# Version1_2.net
KiCad netlist of a schematic drawn in EAGLE
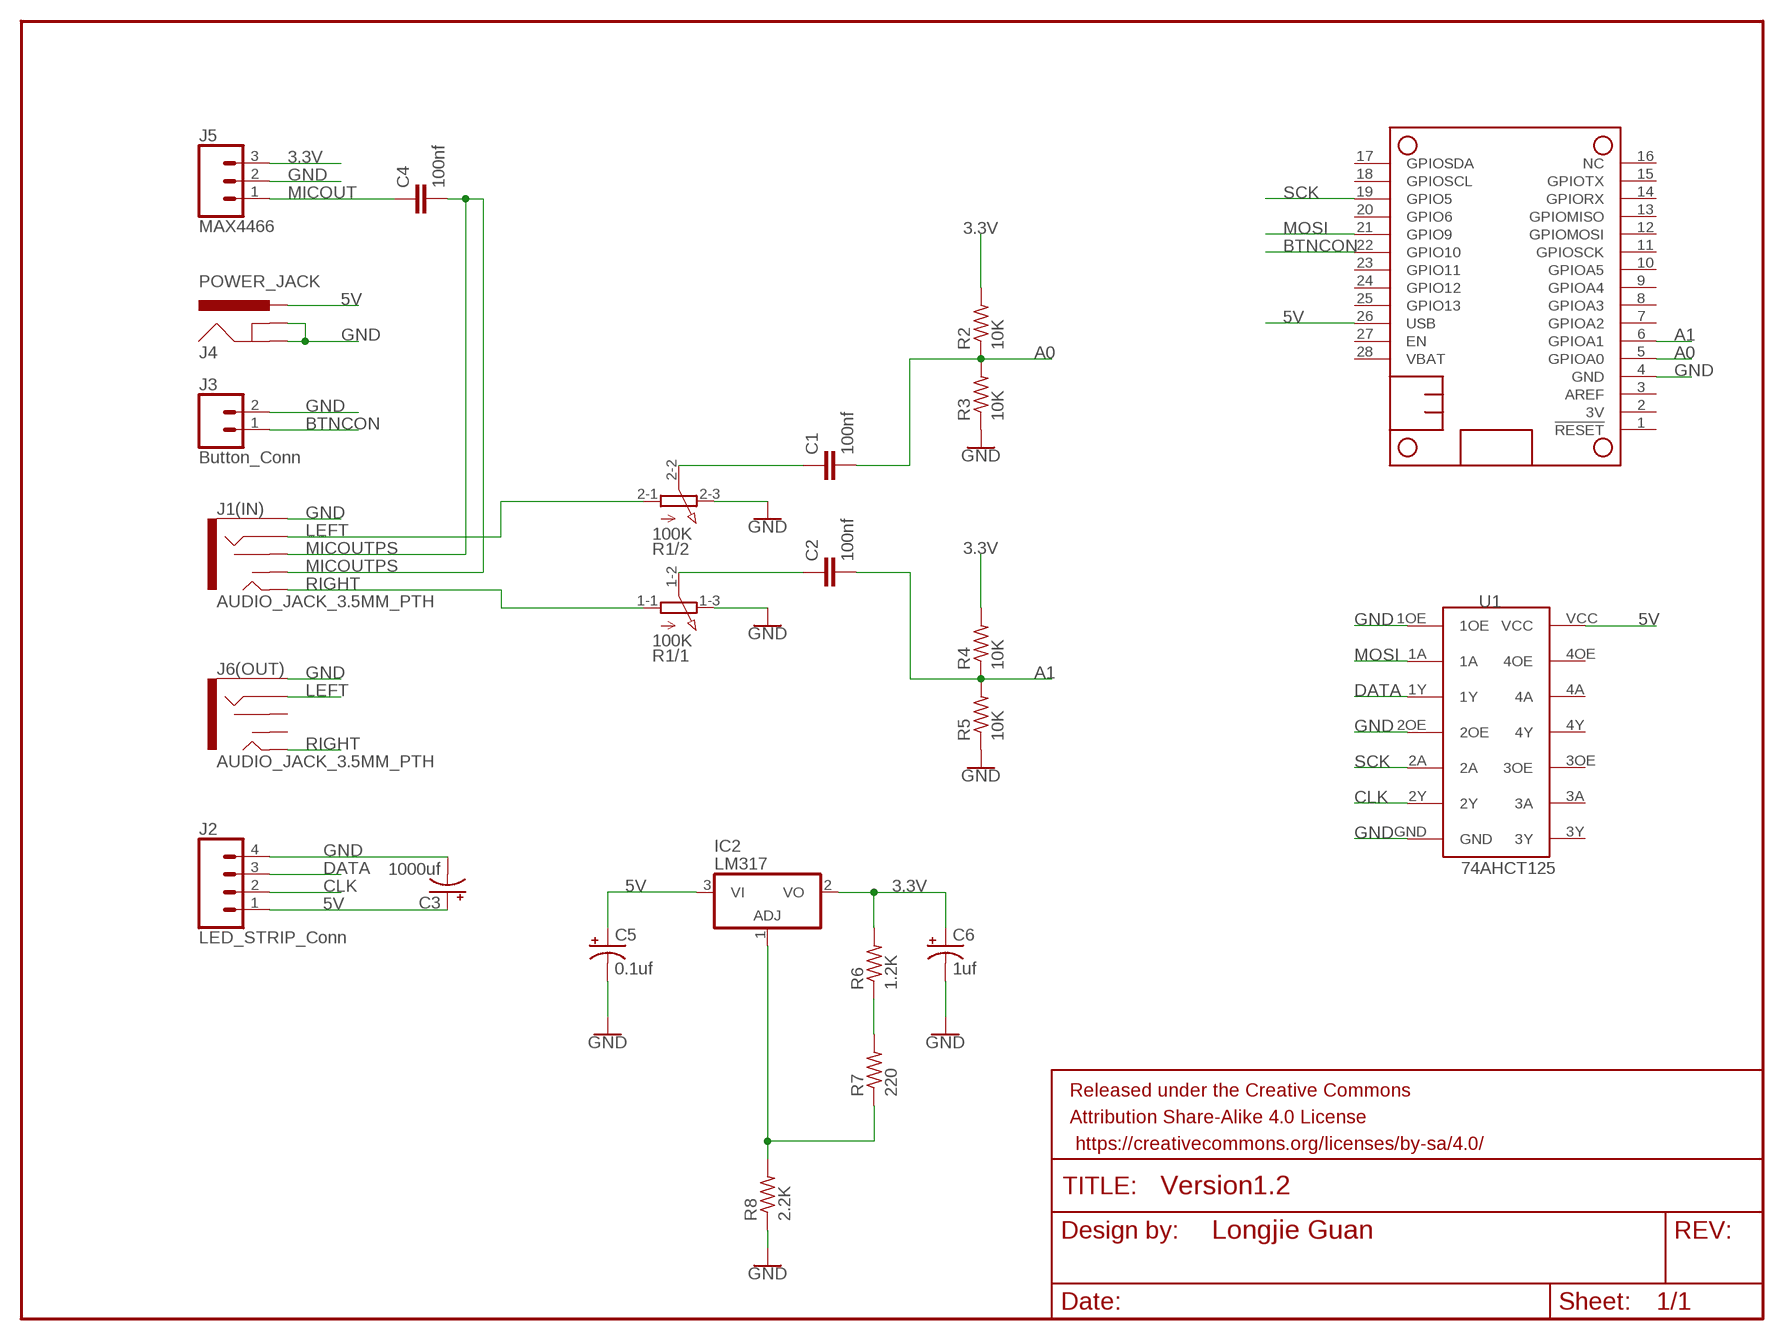
[diagram p0: schematic, sheet 1]

(export (version "E")
  (design (tool "Eeschema 10.0.6"))
  (components
    (comp (ref "C1")
      (value "100nf")
      (footprint "eagle-import:C2.5-2")
      (libsource (lib "eagle-import") (part "C2.5/2"))
    )
    (comp (ref "C2")
      (value "100nf")
      (footprint "eagle-import:C2.5-2")
      (libsource (lib "eagle-import") (part "C2.5/2"))
    )
    (comp (ref "C3")
      (value "1000uf")
      (footprint "eagle-import:B45181A")
      (libsource (lib "eagle-import") (part "CPOL-USB45181A"))
    )
    (comp (ref "C4")
      (value "100nf")
      (footprint "eagle-import:C2.5-2")
      (libsource (lib "eagle-import") (part "C2.5/2"))
    )
    (comp (ref "C5")
      (value "0.1uf")
      (footprint "eagle-import:B45181A")
      (libsource (lib "eagle-import") (part "CPOL-USB45181A"))
    )
    (comp (ref "C6")
      (value "1uf")
      (footprint "eagle-import:B45181A")
      (libsource (lib "eagle-import") (part "CPOL-USB45181A"))
    )
    (comp (ref "FRAME1")
      (value "FRAME-LETTERNO_PACKAGE")
      (footprint "eagle-import:DUMMY")
      (fields (field (name "DESIGNER") "Nobody"))
      (libsource (lib "eagle-import") (part "FRAME-LETTERNO_PACKAGE"))
    )
    (comp (ref "IC2")
      (value "LM317")
      (footprint "eagle-import:TO220H")
      (libsource (lib "eagle-import") (part "317T"))
    )
    (comp (ref "J1(IN)")
      (value "AUDIO_JACK_3.5MM_PTH")
      (footprint "eagle-import:AUDIO-JACK")
      (libsource (lib "eagle-import") (part "AUDIO_JACK_3.5MM_PTH"))
    )
    (comp (ref "J2")
      (value "LED_STRIP_Conn")
      (footprint "eagle-import:1X04_LOCK")
      (libsource (lib "eagle-import") (part "CONN_04LOCK"))
    )
    (comp (ref "J3")
      (value "Button_Conn")
      (footprint "eagle-import:1X02")
      (libsource (lib "eagle-import") (part "CONN_02"))
    )
    (comp (ref "J4")
      (value "POWER_JACK")
      (footprint "eagle-import:POWER_JACK_PTH")
      (libsource (lib "eagle-import") (part "POWER_JACK"))
    )
    (comp (ref "J5")
      (value "MAX4466")
      (footprint "eagle-import:1X03")
      (libsource (lib "eagle-import") (part "CONN_03"))
    )
    (comp (ref "J6(OUT)")
      (value "AUDIO_JACK_3.5MM_PTH")
      (footprint "eagle-import:AUDIO-JACK")
      (libsource (lib "eagle-import") (part "AUDIO_JACK_3.5MM_PTH"))
    )
    (comp (ref "MS1")
      (value "FEATHERWING_NODIM")
      (footprint "eagle-import:FEATHERWING_DIM")
      (libsource (lib "eagle-import") (part "FEATHERWING_NODIM"))
    )
    (comp (ref "R1")
      (value "100K")
      (footprint "eagle-import:3RP_1610G")
      (libsource (lib "eagle-import") (part "3RP/1610G"))
    )
    (comp (ref "R2")
      (value "10K")
      (footprint "eagle-import:0204_7")
      (libsource (lib "eagle-import") (part "R-US_0204/7"))
    )
    (comp (ref "R3")
      (value "10K")
      (footprint "eagle-import:0204_7")
      (libsource (lib "eagle-import") (part "R-US_0204/7"))
    )
    (comp (ref "R4")
      (value "10K")
      (footprint "eagle-import:0204_7")
      (libsource (lib "eagle-import") (part "R-US_0204/7"))
    )
    (comp (ref "R5")
      (value "10K")
      (footprint "eagle-import:0204_7")
      (libsource (lib "eagle-import") (part "R-US_0204/7"))
    )
    (comp (ref "R6")
      (value "1.2K")
      (footprint "eagle-import:0204_7")
      (libsource (lib "eagle-import") (part "R-US_0204/7"))
    )
    (comp (ref "R7")
      (value "220")
      (footprint "eagle-import:0204_7")
      (libsource (lib "eagle-import") (part "R-US_0204/7"))
    )
    (comp (ref "R8")
      (value "2.2K")
      (footprint "eagle-import:0204_7")
      (libsource (lib "eagle-import") (part "R-US_0204/7"))
    )
    (comp (ref "U1")
      (value "74AHCT125")
      (footprint "eagle-import:74AHCT125FP")
      (libsource (lib "eagle-import") (part "74AHCT125TH"))
    )
  )
  (nets
    (net (code "1") (name "/3.3V") (class "Default")
      (node (ref "C6") (pin "+") (pinfunction "+_+") (pintype "passive"))
      (node (ref "IC2") (pin "2") (pinfunction "VO_2") (pintype "passive"))
      (node (ref "J5") (pin "3") (pinfunction "3_3") (pintype "passive"))
      (node (ref "R2") (pin "2") (pinfunction "2_2") (pintype "passive"))
      (node (ref "R4") (pin "2") (pinfunction "2_2") (pintype "passive"))
      (node (ref "R6") (pin "2") (pinfunction "2_2") (pintype "passive"))
    )
    (net (code "2") (name "/3V") (class "Default")
      (node (ref "MS1") (pin "2") (pinfunction "3V_2") (pintype "power_in"))
    )
    (net (code "3") (name "/5V") (class "Default")
      (node (ref "C3") (pin "+") (pinfunction "+_+") (pintype "passive"))
      (node (ref "C5") (pin "+") (pinfunction "+_+") (pintype "passive"))
      (node (ref "IC2") (pin "3") (pinfunction "VI_3") (pintype "input"))
      (node (ref "J2") (pin "1") (pinfunction "1_1") (pintype "passive"))
      (node (ref "J4") (pin "PWR") (pinfunction "PWR_PWR") (pintype "bidirectional"))
      (node (ref "MS1") (pin "26") (pinfunction "USB_26") (pintype "power_in"))
      (node (ref "U1") (pin "VCC") (pinfunction "VCC_VCC") (pintype "bidirectional"))
    )
    (net (code "4") (name "/A0") (class "Default")
      (node (ref "C1") (pin "2") (pinfunction "2_2") (pintype "passive"))
      (node (ref "MS1") (pin "5") (pinfunction "GPIOA0_5") (pintype "bidirectional"))
      (node (ref "R2") (pin "1") (pinfunction "1_1") (pintype "passive"))
      (node (ref "R3") (pin "2") (pinfunction "2_2") (pintype "passive"))
    )
    (net (code "5") (name "/A1") (class "Default")
      (node (ref "C2") (pin "2") (pinfunction "2_2") (pintype "passive"))
      (node (ref "MS1") (pin "6") (pinfunction "GPIOA1_6") (pintype "bidirectional"))
      (node (ref "R4") (pin "1") (pinfunction "1_1") (pintype "passive"))
      (node (ref "R5") (pin "2") (pinfunction "2_2") (pintype "passive"))
    )
    (net (code "6") (name "/BTNCON") (class "Default")
      (node (ref "J3") (pin "1") (pinfunction "1_1") (pintype "passive"))
      (node (ref "MS1") (pin "22") (pinfunction "GPIO10_22") (pintype "bidirectional"))
    )
    (net (code "7") (name "/CLK") (class "Default")
      (node (ref "J2") (pin "2") (pinfunction "2_2") (pintype "passive"))
      (node (ref "U1") (pin "2Y") (pinfunction "2Y_2Y") (pintype "bidirectional"))
    )
    (net (code "8") (name "/DATA") (class "Default")
      (node (ref "J2") (pin "3") (pinfunction "3_3") (pintype "passive"))
      (node (ref "U1") (pin "1Y") (pinfunction "1Y_1Y") (pintype "bidirectional"))
    )
    (net (code "9") (name "/LEFT") (class "Default")
      (node (ref "J1(IN)") (pin "RING") (pinfunction "RING_RING") (pintype "bidirectional"))
      (node (ref "J6(OUT)") (pin "RING") (pinfunction "RING_RING") (pintype "bidirectional"))
      (node (ref "R1") (pin "2-1") (pinfunction "A_2-1") (pintype "passive"))
    )
    (net (code "10") (name "/MICOUT") (class "Default")
      (node (ref "C4") (pin "1") (pinfunction "1_1") (pintype "passive"))
      (node (ref "J5") (pin "1") (pinfunction "1_1") (pintype "passive"))
    )
    (net (code "11") (name "/MICOUTPS") (class "Default")
      (node (ref "C4") (pin "2") (pinfunction "2_2") (pintype "passive"))
      (node (ref "J1(IN)") (pin "RSH") (pinfunction "RSH_RSH") (pintype "bidirectional"))
      (node (ref "J1(IN)") (pin "TSH") (pinfunction "TSH_TSH") (pintype "bidirectional"))
    )
    (net (code "12") (name "/MOSI") (class "Default")
      (node (ref "MS1") (pin "21") (pinfunction "GPIO9_21") (pintype "bidirectional"))
      (node (ref "U1") (pin "1A") (pinfunction "1A_1A") (pintype "bidirectional"))
    )
    (net (code "13") (name "/RIGHT") (class "Default")
      (node (ref "J1(IN)") (pin "TIP") (pinfunction "TIP_TIP") (pintype "bidirectional"))
      (node (ref "J6(OUT)") (pin "TIP") (pinfunction "TIP_TIP") (pintype "bidirectional"))
      (node (ref "R1") (pin "1-1") (pinfunction "A_1-1") (pintype "passive"))
    )
    (net (code "14") (name "/SCK") (class "Default")
      (node (ref "MS1") (pin "19") (pinfunction "GPIO5_19") (pintype "bidirectional"))
      (node (ref "U1") (pin "2A") (pinfunction "2A_2A") (pintype "bidirectional"))
    )
    (net (code "15") (name "/VBAT") (class "Default")
      (node (ref "MS1") (pin "28") (pinfunction "VBAT_28") (pintype "power_in"))
    )
    (net (code "16") (name "GND") (class "Default")
      (node (ref "C3") (pin "-") (pinfunction "-_-") (pintype "passive"))
      (node (ref "C5") (pin "-") (pinfunction "-_-") (pintype "passive"))
      (node (ref "C6") (pin "-") (pinfunction "-_-") (pintype "passive"))
      (node (ref "J1(IN)") (pin "SLEEVE") (pinfunction "SLEEVE_SLEEVE") (pintype "bidirectional"))
      (node (ref "J2") (pin "4") (pinfunction "4_4") (pintype "passive"))
      (node (ref "J3") (pin "2") (pinfunction "2_2") (pintype "passive"))
      (node (ref "J4") (pin "GND") (pinfunction "GND_GND") (pintype "bidirectional"))
      (node (ref "J4") (pin "GNDBREAK") (pinfunction "GNDBREAK_GNDBREAK") (pintype "bidirectional"))
      (node (ref "J5") (pin "2") (pinfunction "2_2") (pintype "passive"))
      (node (ref "J6(OUT)") (pin "SLEEVE") (pinfunction "SLEEVE_SLEEVE") (pintype "bidirectional"))
      (node (ref "MS1") (pin "4") (pinfunction "GND_4") (pintype "power_in"))
      (node (ref "R1") (pin "1-3") (pinfunction "E_1-3") (pintype "passive"))
      (node (ref "R1") (pin "2-3") (pinfunction "E_2-3") (pintype "passive"))
      (node (ref "R3") (pin "1") (pinfunction "1_1") (pintype "passive"))
      (node (ref "R5") (pin "1") (pinfunction "1_1") (pintype "passive"))
      (node (ref "R8") (pin "1") (pinfunction "1_1") (pintype "passive"))
      (node (ref "U1") (pin "1OE") (pinfunction "1OE_1OE") (pintype "bidirectional"))
      (node (ref "U1") (pin "2OE") (pinfunction "2OE_2OE") (pintype "bidirectional"))
      (node (ref "U1") (pin "GND") (pinfunction "GND_GND") (pintype "bidirectional"))
    )
    (net (code "17") (name "Net-(IC2-ADJ)") (class "Default")
      (node (ref "IC2") (pin "1") (pinfunction "ADJ_1") (pintype "input"))
      (node (ref "R7") (pin "1") (pinfunction "1_1") (pintype "passive"))
      (node (ref "R8") (pin "2") (pinfunction "2_2") (pintype "passive"))
    )
    (net (code "18") (name "Net-(R1A-S)") (class "Default")
      (node (ref "C2") (pin "1") (pinfunction "1_1") (pintype "passive"))
      (node (ref "R1") (pin "1-2") (pinfunction "S_1-2") (pintype "passive"))
    )
    (net (code "19") (name "Net-(R1B-S)") (class "Default")
      (node (ref "C1") (pin "1") (pinfunction "1_1") (pintype "passive"))
      (node (ref "R1") (pin "2-2") (pinfunction "S_2-2") (pintype "passive"))
    )
    (net (code "20") (name "Net-(R6-Pad1)") (class "Default")
      (node (ref "R6") (pin "1") (pinfunction "1_1") (pintype "passive"))
      (node (ref "R7") (pin "2") (pinfunction "2_2") (pintype "passive"))
    )
    (net (code "21") (name "unconnected-(J6(OUT)-PadRSH)") (class "Default")
      (node (ref "J6(OUT)") (pin "RSH") (pinfunction "RSH_RSH") (pintype "bidirectional"))
    )
    (net (code "22") (name "unconnected-(J6(OUT)-PadTSH)") (class "Default")
      (node (ref "J6(OUT)") (pin "TSH") (pinfunction "TSH_TSH") (pintype "bidirectional"))
    )
    (net (code "23") (name "unconnected-(MS1-AREF-Pad3)") (class "Default")
      (node (ref "MS1") (pin "3") (pinfunction "AREF_3") (pintype "passive"))
    )
    (net (code "24") (name "unconnected-(MS1-EN-Pad27)") (class "Default")
      (node (ref "MS1") (pin "27") (pinfunction "EN_27") (pintype "passive"))
    )
    (net (code "25") (name "unconnected-(MS1-GPIO6-Pad20)") (class "Default")
      (node (ref "MS1") (pin "20") (pinfunction "GPIO6_20") (pintype "bidirectional"))
    )
    (net (code "26") (name "unconnected-(MS1-GPIO11-Pad23)") (class "Default")
      (node (ref "MS1") (pin "23") (pinfunction "GPIO11_23") (pintype "bidirectional"))
    )
    (net (code "27") (name "unconnected-(MS1-GPIO12-Pad24)") (class "Default")
      (node (ref "MS1") (pin "24") (pinfunction "GPIO12_24") (pintype "bidirectional"))
    )
    (net (code "28") (name "unconnected-(MS1-GPIO13-Pad25)") (class "Default")
      (node (ref "MS1") (pin "25") (pinfunction "GPIO13_25") (pintype "bidirectional"))
    )
    (net (code "29") (name "unconnected-(MS1-GPIOA2-Pad7)") (class "Default")
      (node (ref "MS1") (pin "7") (pinfunction "GPIOA2_7") (pintype "bidirectional"))
    )
    (net (code "30") (name "unconnected-(MS1-GPIOA3-Pad8)") (class "Default")
      (node (ref "MS1") (pin "8") (pinfunction "GPIOA3_8") (pintype "bidirectional"))
    )
    (net (code "31") (name "unconnected-(MS1-GPIOA4-Pad9)") (class "Default")
      (node (ref "MS1") (pin "9") (pinfunction "GPIOA4_9") (pintype "bidirectional"))
    )
    (net (code "32") (name "unconnected-(MS1-GPIOA5-Pad10)") (class "Default")
      (node (ref "MS1") (pin "10") (pinfunction "GPIOA5_10") (pintype "bidirectional"))
    )
    (net (code "33") (name "unconnected-(MS1-GPIOMISO-Pad13)") (class "Default")
      (node (ref "MS1") (pin "13") (pinfunction "GPIOMISO_13") (pintype "bidirectional"))
    )
    (net (code "34") (name "unconnected-(MS1-GPIOMOSI-Pad12)") (class "Default")
      (node (ref "MS1") (pin "12") (pinfunction "GPIOMOSI_12") (pintype "bidirectional"))
    )
    (net (code "35") (name "unconnected-(MS1-GPIORX-Pad14)") (class "Default")
      (node (ref "MS1") (pin "14") (pinfunction "GPIORX_14") (pintype "bidirectional"))
    )
    (net (code "36") (name "unconnected-(MS1-GPIOSCK-Pad11)") (class "Default")
      (node (ref "MS1") (pin "11") (pinfunction "GPIOSCK_11") (pintype "bidirectional"))
    )
    (net (code "37") (name "unconnected-(MS1-GPIOSCL-Pad18)") (class "Default")
      (node (ref "MS1") (pin "18") (pinfunction "GPIOSCL_18") (pintype "bidirectional"))
    )
    (net (code "38") (name "unconnected-(MS1-GPIOSDA-Pad17)") (class "Default")
      (node (ref "MS1") (pin "17") (pinfunction "GPIOSDA_17") (pintype "bidirectional"))
    )
    (net (code "39") (name "unconnected-(MS1-GPIOTX-Pad15)") (class "Default")
      (node (ref "MS1") (pin "15") (pinfunction "GPIOTX_15") (pintype "bidirectional"))
    )
    (net (code "40") (name "unconnected-(MS1-NC-Pad16)") (class "Default")
      (node (ref "MS1") (pin "16") (pinfunction "NC_16") (pintype "passive"))
    )
    (net (code "41") (name "unconnected-(MS1-~{RESET}-Pad1)") (class "Default")
      (node (ref "MS1") (pin "1") (pinfunction "~{RESET}_1") (pintype "input"))
    )
    (net (code "42") (name "unconnected-(U1-Pad3A)") (class "Default")
      (node (ref "U1") (pin "3A") (pinfunction "3A_3A") (pintype "bidirectional"))
    )
    (net (code "43") (name "unconnected-(U1-Pad3OE)") (class "Default")
      (node (ref "U1") (pin "3OE") (pinfunction "3OE_3OE") (pintype "bidirectional"))
    )
    (net (code "44") (name "unconnected-(U1-Pad3Y)") (class "Default")
      (node (ref "U1") (pin "3Y") (pinfunction "3Y_3Y") (pintype "bidirectional"))
    )
    (net (code "45") (name "unconnected-(U1-Pad4A)") (class "Default")
      (node (ref "U1") (pin "4A") (pinfunction "4A_4A") (pintype "bidirectional"))
    )
    (net (code "46") (name "unconnected-(U1-Pad4OE)") (class "Default")
      (node (ref "U1") (pin "4OE") (pinfunction "4OE_4OE") (pintype "bidirectional"))
    )
    (net (code "47") (name "unconnected-(U1-Pad4Y)") (class "Default")
      (node (ref "U1") (pin "4Y") (pinfunction "4Y_4Y") (pintype "bidirectional"))
    )
  )
)
